# ATTiny10ProgrammingAdapter.net
KiCad netlist of a schematic drawn in EAGLE
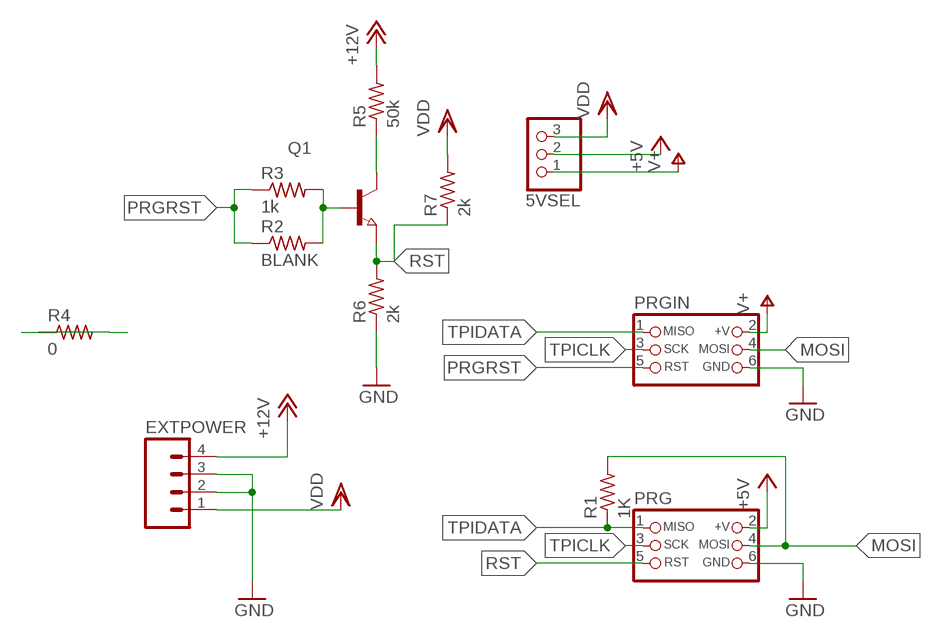
[diagram p0: schematic, sheet 1]

(export (version "E")
  (design (tool "Eeschema 10.0.6"))
  (components
    (comp (ref "5VSEL")
      (value "PINHD-1X3CB")
      (footprint "eagle-import:1X03-CLEANBIG")
      (libsource (lib "eagle-import") (part "PINHD-1X3CB"))
    )
    (comp (ref "EXTPOWER")
      (value "HEADER1X4SMD_LONGPADS")
      (footprint "eagle-import:1X04-SMD-LONG")
      (libsource (lib "eagle-import") (part "HEADER1X4SMD_LONGPADS"))
    )
    (comp (ref "PRG")
      (value "CON_HEADER_PRG_AVR_ICSP_ETCH")
      (footprint "eagle-import:HEADER_PRG_2X03_ETCH")
      (libsource (lib "eagle-import") (part "CON_HEADER_PRG_AVR_ICSP_ETCH"))
    )
    (comp (ref "PRGIN")
      (value "CON_HEADER_PRG_AVR_ICSP_ETCH")
      (footprint "eagle-import:HEADER_PRG_2X03_ETCH")
      (libsource (lib "eagle-import") (part "CON_HEADER_PRG_AVR_ICSP_ETCH"))
    )
    (comp (ref "Q1")
      (value "NPN-TRANSISTOR_SOT23")
      (footprint "eagle-import:SOT23")
      (libsource (lib "eagle-import") (part "NPN-TRANSISTOR_SOT23"))
    )
    (comp (ref "R1")
      (value "1K")
      (footprint "eagle-import:R0805")
      (libsource (lib "eagle-import") (part "R-US_R0805"))
    )
    (comp (ref "R2")
      (value "BLANK")
      (footprint "eagle-import:R0805")
      (libsource (lib "eagle-import") (part "adafruit_R-US_R0805"))
    )
    (comp (ref "R3")
      (value "1k")
      (footprint "eagle-import:R0805")
      (libsource (lib "eagle-import") (part "adafruit_R-US_R0805"))
    )
    (comp (ref "R4")
      (value "0")
      (footprint "eagle-import:R1206")
      (libsource (lib "eagle-import") (part "R-US_R1206"))
    )
    (comp (ref "R5")
      (value "50k")
      (footprint "eagle-import:R0805")
      (libsource (lib "eagle-import") (part "adafruit_R-US_R0805"))
    )
    (comp (ref "R6")
      (value "2k")
      (footprint "eagle-import:R0805")
      (libsource (lib "eagle-import") (part "adafruit_R-US_R0805"))
    )
    (comp (ref "R7")
      (value "2k")
      (footprint "eagle-import:R0805")
      (libsource (lib "eagle-import") (part "adafruit_R-US_R0805"))
    )
  )
  (nets
    (net (code "1") (name "+5V") (class "Default")
      (node (ref "5VSEL") (pin "2") (pinfunction "2_2") (pintype "passive"))
      (node (ref "PRG") (pin "2") (pinfunction "+V_2") (pintype "passive"))
    )
    (net (code "2") (name "+12V") (class "Default")
      (node (ref "EXTPOWER") (pin "4") (pinfunction "4_4") (pintype "passive"))
      (node (ref "R4") (pin "1") (pinfunction "1_1") (pintype "passive"))
      (node (ref "R4") (pin "2") (pinfunction "2_2") (pintype "passive"))
      (node (ref "R5") (pin "2") (pinfunction "2_2") (pintype "passive"))
    )
    (net (code "3") (name "GND") (class "Default")
      (node (ref "EXTPOWER") (pin "2") (pinfunction "2_2") (pintype "passive"))
      (node (ref "EXTPOWER") (pin "3") (pinfunction "3_3") (pintype "passive"))
      (node (ref "PRG") (pin "6") (pinfunction "GND_6") (pintype "passive"))
      (node (ref "PRGIN") (pin "6") (pinfunction "GND_6") (pintype "passive"))
      (node (ref "R6") (pin "1") (pinfunction "1_1") (pintype "passive"))
    )
    (net (code "4") (name "MOSI") (class "Default")
      (node (ref "PRG") (pin "4") (pinfunction "MOSI_4") (pintype "passive"))
      (node (ref "PRGIN") (pin "4") (pinfunction "MOSI_4") (pintype "passive"))
      (node (ref "R1") (pin "2") (pinfunction "2_2") (pintype "passive"))
    )
    (net (code "5") (name "Net-(Q1-B)") (class "Default")
      (node (ref "Q1") (pin "1") (pinfunction "B_1") (pintype "passive"))
      (node (ref "R2") (pin "2") (pinfunction "2_2") (pintype "passive"))
      (node (ref "R3") (pin "2") (pinfunction "2_2") (pintype "passive"))
    )
    (net (code "6") (name "Net-(Q1-C)") (class "Default")
      (node (ref "Q1") (pin "3") (pinfunction "C_3") (pintype "passive"))
      (node (ref "R5") (pin "1") (pinfunction "1_1") (pintype "passive"))
    )
    (net (code "7") (name "PRGRST") (class "Default")
      (node (ref "PRGIN") (pin "5") (pinfunction "RST_5") (pintype "passive"))
      (node (ref "R2") (pin "1") (pinfunction "1_1") (pintype "passive"))
      (node (ref "R3") (pin "1") (pinfunction "1_1") (pintype "passive"))
    )
    (net (code "8") (name "RST") (class "Default")
      (node (ref "PRG") (pin "5") (pinfunction "RST_5") (pintype "passive"))
      (node (ref "Q1") (pin "2") (pinfunction "E_2") (pintype "passive"))
      (node (ref "R6") (pin "2") (pinfunction "2_2") (pintype "passive"))
      (node (ref "R7") (pin "1") (pinfunction "1_1") (pintype "passive"))
    )
    (net (code "9") (name "TPICLK") (class "Default")
      (node (ref "PRG") (pin "3") (pinfunction "SCK_3") (pintype "passive"))
      (node (ref "PRGIN") (pin "3") (pinfunction "SCK_3") (pintype "passive"))
    )
    (net (code "10") (name "TPIDATA") (class "Default")
      (node (ref "PRG") (pin "1") (pinfunction "MISO_1") (pintype "passive"))
      (node (ref "PRGIN") (pin "1") (pinfunction "MISO_1") (pintype "passive"))
      (node (ref "R1") (pin "1") (pinfunction "1_1") (pintype "passive"))
    )
    (net (code "11") (name "V+") (class "Default")
      (node (ref "5VSEL") (pin "1") (pinfunction "1_1") (pintype "passive"))
      (node (ref "PRGIN") (pin "2") (pinfunction "+V_2") (pintype "passive"))
    )
    (net (code "12") (name "VDD") (class "Default")
      (node (ref "5VSEL") (pin "3") (pinfunction "3_3") (pintype "passive"))
      (node (ref "EXTPOWER") (pin "1") (pinfunction "1_1") (pintype "passive"))
      (node (ref "R7") (pin "2") (pinfunction "2_2") (pintype "passive"))
    )
  )
)
